# MTX_pic_piggyback_BRW_V13.net
KiCad netlist of a schematic drawn in EAGLE
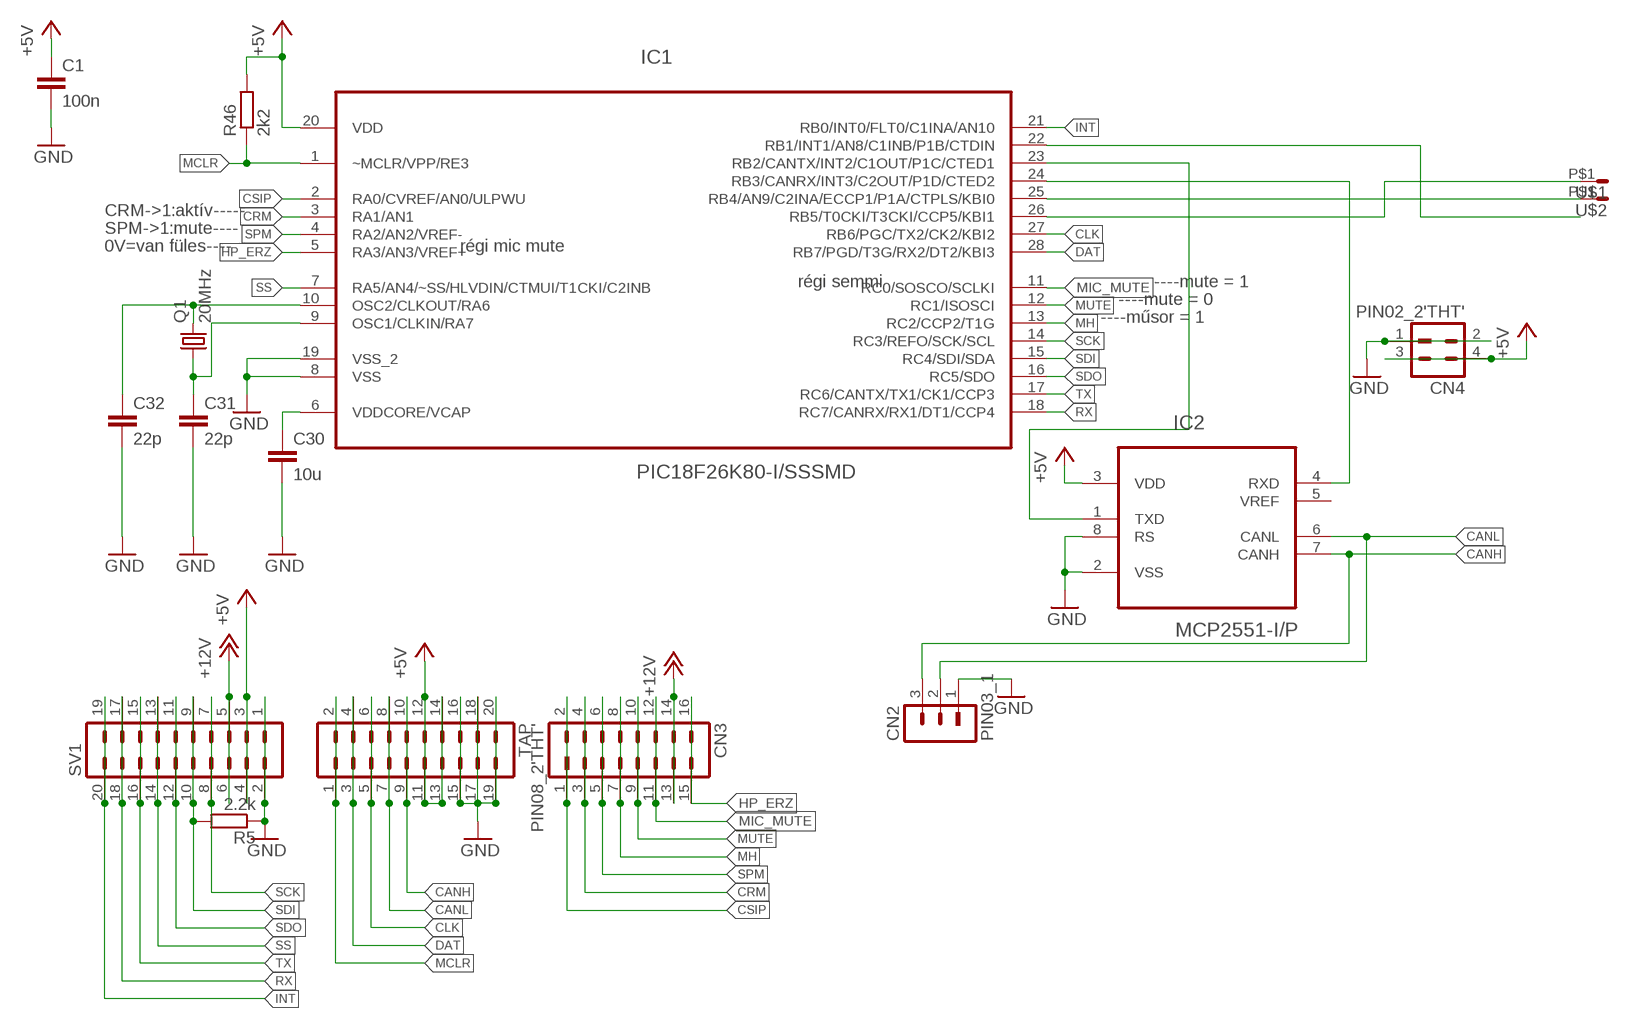
[diagram p0: schematic, sheet 1]

(export (version "E")
  (design (tool "Eeschema 10.0.6"))
  (components
    (comp (ref "C1")
      (value "100n")
      (footprint "eagle-import:C0805")
      (libsource (lib "eagle-import") (part "C-EUC0805"))
    )
    (comp (ref "C30")
      (value "10u")
      (footprint "eagle-import:C0805")
      (libsource (lib "eagle-import") (part "C-EUC0805"))
    )
    (comp (ref "C31")
      (value "22p")
      (footprint "eagle-import:C0805")
      (libsource (lib "eagle-import") (part "C-EUC0805"))
    )
    (comp (ref "C32")
      (value "22p")
      (footprint "eagle-import:C0805")
      (libsource (lib "eagle-import") (part "C-EUC0805"))
    )
    (comp (ref "CN2")
      (value "PIN03_1")
      (footprint "eagle-import:PIN03_1")
      (libsource (lib "eagle-import") (part "PIN03_1"))
    )
    (comp (ref "CN3")
      (value "PIN08_2'THT'")
      (footprint "eagle-import:PIN08_2")
      (libsource (lib "eagle-import") (part "PIN08_2'THT'"))
    )
    (comp (ref "CN4")
      (value "PIN02_2'THT'")
      (footprint "eagle-import:PIN02_2")
      (libsource (lib "eagle-import") (part "PIN02_2'THT'"))
    )
    (comp (ref "IC1")
      (value "PIC18F26K80-I/SSSMD")
      (footprint "eagle-import:SOP65P780X200-28N")
      (libsource (lib "eagle-import") (part "PIC18F25K80-I/SSSMD"))
    )
    (comp (ref "IC2")
      (value "MCP2551-I/P")
      (footprint "eagle-import:DIP254P762X432-8")
      (libsource (lib "eagle-import") (part "MCP2551-I/P"))
    )
    (comp (ref "Q1")
      (value "20MHz")
      (footprint "eagle-import:XTAL_QS")
      (libsource (lib "eagle-import") (part "XTAL_2QS"))
    )
    (comp (ref "R5")
      (value "2.2k")
      (footprint "eagle-import:R0805")
      (libsource (lib "eagle-import") (part "R-EU_R0805"))
    )
    (comp (ref "R46")
      (value "2k2")
      (footprint "eagle-import:R0805")
      (libsource (lib "eagle-import") (part "R-EU_R0805"))
    )
    (comp (ref "SV1")
      (value "MA10-2")
      (footprint "eagle-import:MA10-2")
      (libsource (lib "eagle-import") (part "MA10-2"))
    )
    (comp (ref "TAP")
      (value "MA10-2")
      (footprint "eagle-import:MA10-2")
      (libsource (lib "eagle-import") (part "MA10-2"))
    )
    (comp (ref "U$1")
      (value "PADSMD")
      (footprint "eagle-import:PAD_SMD")
      (libsource (lib "eagle-import") (part "PADSMD"))
    )
    (comp (ref "U$2")
      (value "PADSMD")
      (footprint "eagle-import:PAD_SMD")
      (libsource (lib "eagle-import") (part "PADSMD"))
    )
  )
  (nets
    (net (code "1") (name "+5V") (class "Default")
      (node (ref "C1") (pin "1") (pinfunction "1_1") (pintype "passive"))
      (node (ref "CN4") (pin "3") (pinfunction "3_3") (pintype "passive"))
      (node (ref "CN4") (pin "4") (pinfunction "4_4") (pintype "passive"))
      (node (ref "IC1") (pin "20") (pinfunction "VDD_20") (pintype "power_in"))
      (node (ref "IC2") (pin "3") (pinfunction "VDD_3") (pintype "power_in"))
      (node (ref "R46") (pin "2") (pinfunction "2_2") (pintype "passive"))
      (node (ref "SV1") (pin "3") (pinfunction "3_3") (pintype "passive"))
      (node (ref "SV1") (pin "4") (pinfunction "4_4") (pintype "passive"))
      (node (ref "TAP") (pin "11") (pinfunction "11_11") (pintype "passive"))
      (node (ref "TAP") (pin "12") (pinfunction "12_12") (pintype "passive"))
      (node (ref "TAP") (pin "13") (pinfunction "13_13") (pintype "passive"))
      (node (ref "TAP") (pin "14") (pinfunction "14_14") (pintype "passive"))
    )
    (net (code "2") (name "+12V") (class "Default")
      (node (ref "CN3") (pin "13") (pinfunction "13_13") (pintype "passive"))
      (node (ref "CN3") (pin "14") (pinfunction "14_14") (pintype "passive"))
      (node (ref "SV1") (pin "5") (pinfunction "5_5") (pintype "passive"))
      (node (ref "SV1") (pin "6") (pinfunction "6_6") (pintype "passive"))
    )
    (net (code "3") (name "CANH") (class "Default")
      (node (ref "CN2") (pin "3") (pinfunction "3_3") (pintype "passive"))
      (node (ref "IC2") (pin "7") (pinfunction "CANH_7") (pintype "bidirectional"))
      (node (ref "TAP") (pin "10") (pinfunction "10_10") (pintype "passive"))
      (node (ref "TAP") (pin "9") (pinfunction "9_9") (pintype "passive"))
    )
    (net (code "4") (name "CANL") (class "Default")
      (node (ref "CN2") (pin "2") (pinfunction "2_2") (pintype "passive"))
      (node (ref "IC2") (pin "6") (pinfunction "CANL_6") (pintype "bidirectional"))
      (node (ref "TAP") (pin "7") (pinfunction "7_7") (pintype "passive"))
      (node (ref "TAP") (pin "8") (pinfunction "8_8") (pintype "passive"))
    )
    (net (code "5") (name "CLK") (class "Default")
      (node (ref "IC1") (pin "27") (pinfunction "RB6/PGC/TX2/CK2/KBI2_27") (pintype "bidirectional"))
      (node (ref "TAP") (pin "5") (pinfunction "5_5") (pintype "passive"))
      (node (ref "TAP") (pin "6") (pinfunction "6_6") (pintype "passive"))
    )
    (net (code "6") (name "CRM") (class "Default")
      (node (ref "CN3") (pin "3") (pinfunction "3_3") (pintype "passive"))
      (node (ref "CN3") (pin "4") (pinfunction "4_4") (pintype "passive"))
      (node (ref "IC1") (pin "3") (pinfunction "RA1/AN1_3") (pintype "bidirectional"))
    )
    (net (code "7") (name "CSIP") (class "Default")
      (node (ref "CN3") (pin "1") (pinfunction "1_1") (pintype "passive"))
      (node (ref "CN3") (pin "2") (pinfunction "2_2") (pintype "passive"))
      (node (ref "IC1") (pin "2") (pinfunction "RA0/CVREF/AN0/ULPWU_2") (pintype "bidirectional"))
    )
    (net (code "8") (name "DAT") (class "Default")
      (node (ref "IC1") (pin "28") (pinfunction "RB7/PGD/T3G/RX2/DT2/KBI3_28") (pintype "bidirectional"))
      (node (ref "TAP") (pin "3") (pinfunction "3_3") (pintype "passive"))
      (node (ref "TAP") (pin "4") (pinfunction "4_4") (pintype "passive"))
    )
    (net (code "9") (name "GND") (class "Default")
      (node (ref "C1") (pin "2") (pinfunction "2_2") (pintype "passive"))
      (node (ref "C30") (pin "2") (pinfunction "2_2") (pintype "passive"))
      (node (ref "C31") (pin "2") (pinfunction "2_2") (pintype "passive"))
      (node (ref "C32") (pin "2") (pinfunction "2_2") (pintype "passive"))
      (node (ref "CN2") (pin "1") (pinfunction "1_1") (pintype "passive"))
      (node (ref "CN4") (pin "1") (pinfunction "1_1") (pintype "passive"))
      (node (ref "CN4") (pin "2") (pinfunction "2_2") (pintype "passive"))
      (node (ref "IC1") (pin "19") (pinfunction "VSS_2_19") (pintype "power_in"))
      (node (ref "IC1") (pin "8") (pinfunction "VSS_8") (pintype "power_in"))
      (node (ref "IC2") (pin "2") (pinfunction "VSS_2") (pintype "power_in"))
      (node (ref "IC2") (pin "8") (pinfunction "RS_8") (pintype "input"))
      (node (ref "R5") (pin "1") (pinfunction "1_1") (pintype "passive"))
      (node (ref "SV1") (pin "1") (pinfunction "1_1") (pintype "passive"))
      (node (ref "SV1") (pin "2") (pinfunction "2_2") (pintype "passive"))
      (node (ref "TAP") (pin "15") (pinfunction "15_15") (pintype "passive"))
      (node (ref "TAP") (pin "16") (pinfunction "16_16") (pintype "passive"))
      (node (ref "TAP") (pin "17") (pinfunction "17_17") (pintype "passive"))
      (node (ref "TAP") (pin "18") (pinfunction "18_18") (pintype "passive"))
      (node (ref "TAP") (pin "19") (pinfunction "19_19") (pintype "passive"))
      (node (ref "TAP") (pin "20") (pinfunction "20_20") (pintype "passive"))
    )
    (net (code "10") (name "HP_ERZ") (class "Default")
      (node (ref "CN3") (pin "15") (pinfunction "15_15") (pintype "passive"))
      (node (ref "CN3") (pin "16") (pinfunction "16_16") (pintype "passive"))
      (node (ref "IC1") (pin "5") (pinfunction "RA3/AN3/VREF+_5") (pintype "bidirectional"))
    )
    (net (code "11") (name "INT") (class "Default")
      (node (ref "IC1") (pin "21") (pinfunction "RB0/INT0/FLT0/C1INA/AN10_21") (pintype "bidirectional"))
      (node (ref "SV1") (pin "19") (pinfunction "19_19") (pintype "passive"))
      (node (ref "SV1") (pin "20") (pinfunction "20_20") (pintype "passive"))
    )
    (net (code "12") (name "MCLR") (class "Default")
      (node (ref "IC1") (pin "1") (pinfunction "~{MCLR/VPP/RE3}_1") (pintype "input"))
      (node (ref "R46") (pin "1") (pinfunction "1_1") (pintype "passive"))
      (node (ref "TAP") (pin "1") (pinfunction "1_1") (pintype "passive"))
      (node (ref "TAP") (pin "2") (pinfunction "2_2") (pintype "passive"))
    )
    (net (code "13") (name "MH") (class "Default")
      (node (ref "CN3") (pin "7") (pinfunction "7_7") (pintype "passive"))
      (node (ref "CN3") (pin "8") (pinfunction "8_8") (pintype "passive"))
      (node (ref "IC1") (pin "13") (pinfunction "RC2/CCP2/T1G_13") (pintype "bidirectional"))
    )
    (net (code "14") (name "MIC_MUTE") (class "Default")
      (node (ref "CN3") (pin "11") (pinfunction "11_11") (pintype "passive"))
      (node (ref "CN3") (pin "12") (pinfunction "12_12") (pintype "passive"))
      (node (ref "IC1") (pin "11") (pinfunction "RC0/SOSCO/SCLKI_11") (pintype "bidirectional"))
    )
    (net (code "15") (name "MUTE") (class "Default")
      (node (ref "CN3") (pin "10") (pinfunction "10_10") (pintype "passive"))
      (node (ref "CN3") (pin "9") (pinfunction "9_9") (pintype "passive"))
      (node (ref "IC1") (pin "12") (pinfunction "RC1/ISOSCI_12") (pintype "bidirectional"))
    )
    (net (code "16") (name "Net-(IC1-OSC1{slash}CLKIN{slash}RA7)") (class "Default")
      (node (ref "C31") (pin "1") (pinfunction "1_1") (pintype "passive"))
      (node (ref "IC1") (pin "9") (pinfunction "OSC1/CLKIN/RA7_9") (pintype "bidirectional"))
      (node (ref "Q1") (pin "1") (pinfunction "1_1") (pintype "passive"))
    )
    (net (code "17") (name "Net-(IC1-OSC2{slash}CLKOUT{slash}RA6)") (class "Default")
      (node (ref "C32") (pin "1") (pinfunction "1_1") (pintype "passive"))
      (node (ref "IC1") (pin "10") (pinfunction "OSC2/CLKOUT/RA6_10") (pintype "bidirectional"))
      (node (ref "Q1") (pin "2") (pinfunction "2_2") (pintype "passive"))
    )
    (net (code "18") (name "Net-(IC1-RB2{slash}CANTX{slash}INT2{slash}C1OUT{slash}P1C{slash}CTED1)") (class "Default")
      (node (ref "IC1") (pin "23") (pinfunction "RB2/CANTX/INT2/C1OUT/P1C/CTED1_23") (pintype "bidirectional"))
      (node (ref "IC2") (pin "1") (pinfunction "TXD_1") (pintype "input"))
    )
    (net (code "19") (name "Net-(IC1-RB3{slash}CANRX{slash}INT3{slash}C2OUT{slash}P1D{slash}CTED2)") (class "Default")
      (node (ref "IC1") (pin "24") (pinfunction "RB3/CANRX/INT3/C2OUT/P1D/CTED2_24") (pintype "bidirectional"))
      (node (ref "IC2") (pin "4") (pinfunction "RXD_4") (pintype "output"))
    )
    (net (code "20") (name "Net-(IC1-RB4{slash}AN9{slash}C2INA{slash}ECCP1{slash}P1A{slash}CTPLS{slash}KBI0)") (class "Default")
      (node (ref "IC1") (pin "25") (pinfunction "RB4/AN9/C2INA/ECCP1/P1A/CTPLS/KBI0_25") (pintype "bidirectional"))
      (node (ref "U$2") (pin "P$1") (pinfunction "2_P$1") (pintype "passive"))
    )
    (net (code "21") (name "Net-(IC1-RB5{slash}T0CKI{slash}T3CKI{slash}CCP5{slash}KBI1)") (class "Default")
      (node (ref "IC1") (pin "26") (pinfunction "RB5/T0CKI/T3CKI/CCP5/KBI1_26") (pintype "bidirectional"))
      (node (ref "U$1") (pin "P$1") (pinfunction "2_P$1") (pintype "passive"))
    )
    (net (code "22") (name "Net-(IC1-VDDCORE{slash}VCAP)") (class "Default")
      (node (ref "C30") (pin "1") (pinfunction "1_1") (pintype "passive"))
      (node (ref "IC1") (pin "6") (pinfunction "VDDCORE/VCAP_6") (pintype "bidirectional"))
    )
    (net (code "23") (name "RX") (class "Default")
      (node (ref "IC1") (pin "18") (pinfunction "RC7/CANRX/RX1/DT1/CCP4_18") (pintype "bidirectional"))
      (node (ref "SV1") (pin "17") (pinfunction "17_17") (pintype "passive"))
      (node (ref "SV1") (pin "18") (pinfunction "18_18") (pintype "passive"))
    )
    (net (code "24") (name "SCK") (class "Default")
      (node (ref "IC1") (pin "14") (pinfunction "RC3/REFO/SCK/SCL_14") (pintype "bidirectional"))
      (node (ref "SV1") (pin "7") (pinfunction "7_7") (pintype "passive"))
      (node (ref "SV1") (pin "8") (pinfunction "8_8") (pintype "passive"))
    )
    (net (code "25") (name "SDI") (class "Default")
      (node (ref "IC1") (pin "15") (pinfunction "RC4/SDI/SDA_15") (pintype "bidirectional"))
      (node (ref "R5") (pin "2") (pinfunction "2_2") (pintype "passive"))
      (node (ref "SV1") (pin "10") (pinfunction "10_10") (pintype "passive"))
      (node (ref "SV1") (pin "9") (pinfunction "9_9") (pintype "passive"))
    )
    (net (code "26") (name "SDO") (class "Default")
      (node (ref "IC1") (pin "16") (pinfunction "RC5/SDO_16") (pintype "bidirectional"))
      (node (ref "SV1") (pin "11") (pinfunction "11_11") (pintype "passive"))
      (node (ref "SV1") (pin "12") (pinfunction "12_12") (pintype "passive"))
    )
    (net (code "27") (name "SPM") (class "Default")
      (node (ref "CN3") (pin "5") (pinfunction "5_5") (pintype "passive"))
      (node (ref "CN3") (pin "6") (pinfunction "6_6") (pintype "passive"))
      (node (ref "IC1") (pin "4") (pinfunction "RA2/AN2/VREF-_4") (pintype "bidirectional"))
    )
    (net (code "28") (name "SS") (class "Default")
      (node (ref "IC1") (pin "7") (pinfunction "RA5/AN4/~{SS/HLVDIN/CTMUI/T1CKI/C2INB}_7") (pintype "bidirectional"))
      (node (ref "SV1") (pin "13") (pinfunction "13_13") (pintype "passive"))
      (node (ref "SV1") (pin "14") (pinfunction "14_14") (pintype "passive"))
    )
    (net (code "29") (name "TX") (class "Default")
      (node (ref "IC1") (pin "17") (pinfunction "RC6/CANTX/TX1/CK1/CCP3_17") (pintype "bidirectional"))
      (node (ref "SV1") (pin "15") (pinfunction "15_15") (pintype "passive"))
      (node (ref "SV1") (pin "16") (pinfunction "16_16") (pintype "passive"))
    )
    (net (code "30") (name "unconnected-(IC1-RB1{slash}INT1{slash}AN8{slash}C1INB{slash}P1B{slash}CTDIN-Pad22)") (class "Default")
      (node (ref "IC1") (pin "22") (pinfunction "RB1/INT1/AN8/C1INB/P1B/CTDIN_22") (pintype "bidirectional"))
    )
    (net (code "31") (name "unconnected-(IC2-VREF-Pad5)") (class "Default")
      (node (ref "IC2") (pin "5") (pinfunction "VREF_5") (pintype "output"))
    )
  )
)
